# mp28164-buck-boost-flashlight-driver-tes.net
KiCad netlist of a schematic drawn in EAGLE
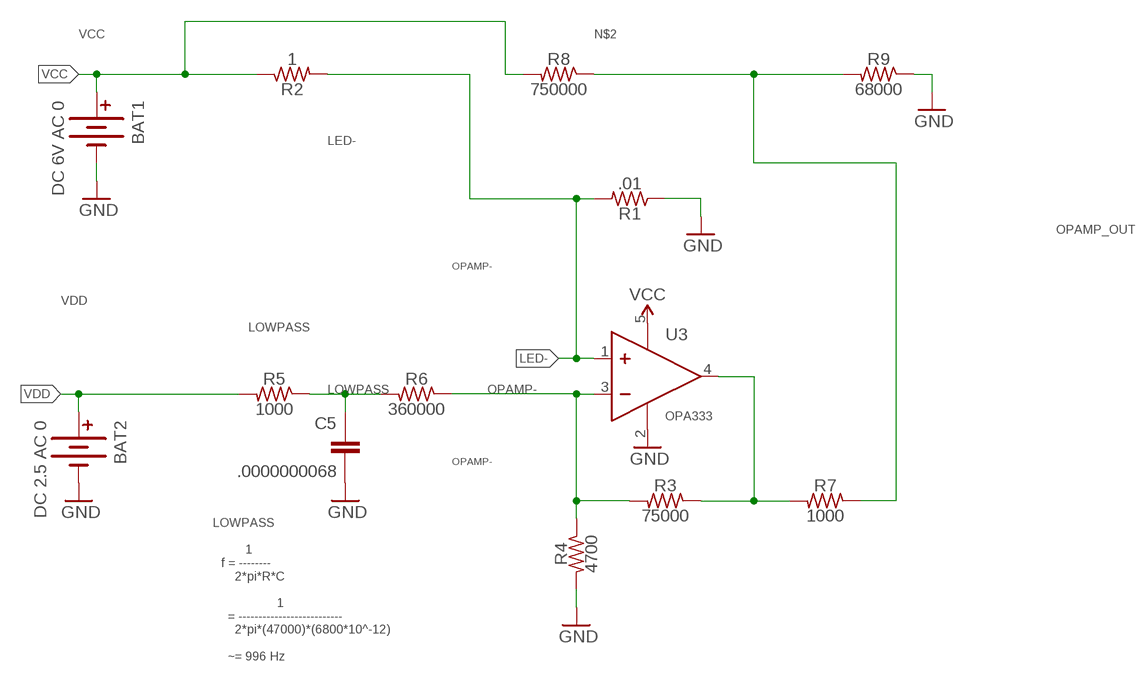
[diagram p0: schematic, sheet 1]

(export (version "E")
  (design (tool "Eeschema 10.0.6"))
  (components
    (comp (ref "BAT1")
      (value "DC 6V AC 0")
      (footprint "eagle-import:BATTCON_9V")
      (fields (field (name "SPICEPREFIX") "V"))
      (libsource (lib "eagle-import") (part "BATTERY9V"))
    )
    (comp (ref "BAT2")
      (value "DC 2.5 AC 0")
      (footprint "eagle-import:BATTCON_9V")
      (fields (field (name "SPICEPREFIX") "V"))
      (libsource (lib "eagle-import") (part "BATTERY9V"))
    )
    (comp (ref "C5")
      (value ".0000000068")
      (footprint "eagle-import:C0402")
      (fields (field (name "SPICEPREFIX") "C"))
      (libsource (lib "eagle-import") (part "CAPACITOR-CERAMICC0402"))
    )
    (comp (ref "R1")
      (value ".01")
      (footprint "eagle-import:R0805-TIGHTER")
      (fields (field (name "SPICEPREFIX") "R"))
      (libsource (lib "eagle-import") (part "RESISTORR0805-TIGHTER"))
    )
    (comp (ref "R2")
      (value "1")
      (footprint "eagle-import:R0402")
      (fields (field (name "SPICEPREFIX") "R"))
      (libsource (lib "eagle-import") (part "RESISTORR0402"))
    )
    (comp (ref "R3")
      (value "75000")
      (footprint "eagle-import:R0402")
      (fields (field (name "SPICEPREFIX") "R"))
      (libsource (lib "eagle-import") (part "RESISTORR0402"))
    )
    (comp (ref "R4")
      (value "4700")
      (footprint "eagle-import:R0402")
      (fields (field (name "SPICEPREFIX") "R"))
      (libsource (lib "eagle-import") (part "RESISTORR0402"))
    )
    (comp (ref "R5")
      (value "1000")
      (footprint "eagle-import:R0402")
      (fields (field (name "SPICEPREFIX") "R"))
      (libsource (lib "eagle-import") (part "RESISTORR0402"))
    )
    (comp (ref "R6")
      (value "360000")
      (footprint "eagle-import:R0402")
      (fields (field (name "SPICEPREFIX") "R"))
      (libsource (lib "eagle-import") (part "RESISTORR0402"))
    )
    (comp (ref "R7")
      (value "1000")
      (footprint "eagle-import:R0402")
      (fields (field (name "SPICEPREFIX") "R"))
      (libsource (lib "eagle-import") (part "RESISTORR0402"))
    )
    (comp (ref "R8")
      (value "750000")
      (footprint "eagle-import:R0402")
      (fields (field (name "SPICEPREFIX") "R"))
      (libsource (lib "eagle-import") (part "RESISTORR0402"))
    )
    (comp (ref "R9")
      (value "68000")
      (footprint "eagle-import:R0402")
      (fields (field (name "SPICEPREFIX") "R"))
      (libsource (lib "eagle-import") (part "RESISTORR0402"))
    )
    (comp (ref "U3")
      (value "OPA333")
      (footprint "eagle-import:SC70")
      (fields (field (name "SPICEMODEL") "OPAMP") (field (name "SPICEPREFIX") "X"))
      (libsource (lib "eagle-import") (part "OPAMPOPA333-SC-70"))
    )
  )
  (nets
    (net (code "1") (name "/LOWPASS") (class "Default")
      (node (ref "C5") (pin "1") (pinfunction "1_1") (pintype "passive"))
      (node (ref "R5") (pin "1") (pinfunction "1_1") (pintype "passive"))
      (node (ref "R6") (pin "2") (pinfunction "2_2") (pintype "passive"))
    )
    (net (code "2") (name "/OPAMP-") (class "Default")
      (node (ref "R3") (pin "2") (pinfunction "2_2") (pintype "passive"))
      (node (ref "R4") (pin "1") (pinfunction "1_1") (pintype "passive"))
      (node (ref "R6") (pin "1") (pinfunction "1_1") (pintype "passive"))
      (node (ref "U3") (pin "3") (pinfunction "IN-_3") (pintype "input"))
    )
    (net (code "3") (name "GND") (class "Default")
      (node (ref "BAT1") (pin "-") (pinfunction "-_-") (pintype "power_in"))
      (node (ref "BAT2") (pin "-") (pinfunction "-_-") (pintype "power_in"))
      (node (ref "C5") (pin "2") (pinfunction "2_2") (pintype "passive"))
      (node (ref "R1") (pin "1") (pinfunction "1_1") (pintype "passive"))
      (node (ref "R4") (pin "2") (pinfunction "2_2") (pintype "passive"))
      (node (ref "R9") (pin "1") (pinfunction "1_1") (pintype "passive"))
      (node (ref "U3") (pin "2") (pinfunction "V-_2") (pintype "power_in"))
    )
    (net (code "4") (name "LED-") (class "Default")
      (node (ref "R1") (pin "2") (pinfunction "2_2") (pintype "passive"))
      (node (ref "R2") (pin "2") (pinfunction "2_2") (pintype "passive"))
      (node (ref "U3") (pin "1") (pinfunction "IN+_1") (pintype "input"))
    )
    (net (code "5") (name "Net-(R7-Pad1)") (class "Default")
      (node (ref "R7") (pin "1") (pinfunction "1_1") (pintype "passive"))
      (node (ref "R8") (pin "1") (pinfunction "1_1") (pintype "passive"))
      (node (ref "R9") (pin "2") (pinfunction "2_2") (pintype "passive"))
    )
    (net (code "6") (name "Net-(U3-OUT)") (class "Default")
      (node (ref "R3") (pin "1") (pinfunction "1_1") (pintype "passive"))
      (node (ref "R7") (pin "2") (pinfunction "2_2") (pintype "passive"))
      (node (ref "U3") (pin "4") (pinfunction "OUT_4") (pintype "output"))
    )
    (net (code "7") (name "VCC") (class "Default")
      (node (ref "BAT1") (pin "+") (pinfunction "+_+") (pintype "power_in"))
      (node (ref "R2") (pin "1") (pinfunction "1_1") (pintype "passive"))
      (node (ref "R8") (pin "2") (pinfunction "2_2") (pintype "passive"))
      (node (ref "U3") (pin "5") (pinfunction "V+_5") (pintype "power_in"))
    )
    (net (code "8") (name "VDD") (class "Default")
      (node (ref "BAT2") (pin "+") (pinfunction "+_+") (pintype "power_in"))
      (node (ref "R5") (pin "2") (pinfunction "2_2") (pintype "passive"))
    )
  )
)
